# Sheet1.net
KiCad netlist of a schematic drawn in Altium Designer
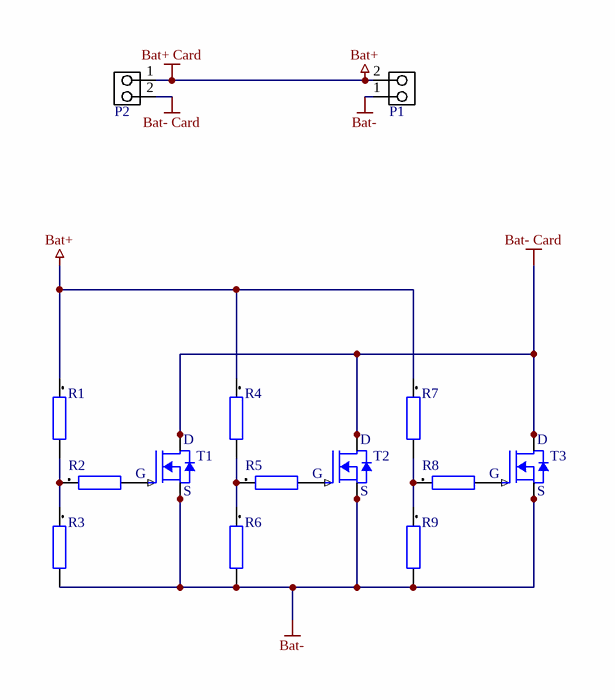
[diagram p0: Sheet1.SchDoc]

(export (version "E")
  (design (tool "Eeschema 10.0.6"))
  (components
    (comp (ref "P1")
      (value "2 power pads")
      (footprint "PowerPads 2 pins")
      (description "2-Pin")
      (fields (field (name "MANUFACTURER") "Generic Components") (field (name "PUBLISHER") "Altium Limited"))
      (libsource (lib "") (part "2 power pads_1"))
    )
    (comp (ref "P2")
      (value "2 power pads")
      (footprint "PowerPads 2 pins")
      (description "2-Pin")
      (fields (field (name "MANUFACTURER") "Generic Components") (field (name "PUBLISHER") "Altium Limited"))
      (libsource (lib "Schlib") (part "2 power pads"))
    )
    (comp (ref "R1")
      (value "TBD")
      (footprint "RESC1608X06L")
      (description "Resistor ToDo 0603")
      (libsource (lib "LSRO1Altium") (part "RES"))
    )
    (comp (ref "R2")
      (value "TBD")
      (footprint "RESC1608X06L")
      (description "Resistor ToDo 0603")
      (libsource (lib "LSRO1Altium") (part "RES"))
    )
    (comp (ref "R3")
      (value "TBD")
      (footprint "RESC1608X06L")
      (description "Resistor ToDo 0603")
      (libsource (lib "LSRO1Altium") (part "RES"))
    )
    (comp (ref "R4")
      (value "TBD")
      (footprint "RESC1608X06L")
      (description "Resistor ToDo 0603")
      (libsource (lib "LSRO1Altium") (part "RES"))
    )
    (comp (ref "R5")
      (value "TBD")
      (footprint "RESC1608X06L")
      (description "Resistor ToDo 0603")
      (libsource (lib "LSRO1Altium") (part "RES"))
    )
    (comp (ref "R6")
      (value "TBD")
      (footprint "RESC1608X06L")
      (description "Resistor ToDo 0603")
      (libsource (lib "LSRO1Altium") (part "RES"))
    )
    (comp (ref "R7")
      (value "TBD")
      (footprint "RESC1608X06L")
      (description "Resistor ToDo 0603")
      (libsource (lib "LSRO1Altium") (part "RES"))
    )
    (comp (ref "R8")
      (value "TBD")
      (footprint "RESC1608X06L")
      (description "Resistor ToDo 0603")
      (libsource (lib "LSRO1Altium") (part "RES"))
    )
    (comp (ref "R9")
      (value "TBD")
      (footprint "RESC1608X06L")
      (description "Resistor ToDo 0603")
      (libsource (lib "LSRO1Altium") (part "RES"))
    )
    (comp (ref "T1")
      (value "FDMC8010DC")
      (footprint "PQFN8 3.3X3.3")
      (fields (field (name "MANUFACTURER") "ON Semiconductor / Fairchild"))
      (libsource (lib "Schlib1") (part "FDMC8010DC"))
    )
    (comp (ref "T2")
      (value "FDMC8010DC")
      (footprint "PQFN8 3.3X3.3")
      (fields (field (name "MANUFACTURER") "ON Semiconductor / Fairchild"))
      (libsource (lib "Schlib1") (part "FDMC8010DC"))
    )
    (comp (ref "T3")
      (value "FDMC8010DC")
      (footprint "PQFN8 3.3X3.3")
      (fields (field (name "MANUFACTURER") "ON Semiconductor / Fairchild"))
      (libsource (lib "Schlib1") (part "FDMC8010DC"))
    )
  )
  (nets
    (net (code "1") (name "Bat+") (class "Default")
      (node (ref "P1") (pin "2") (pinfunction "2_2") (pintype "passive"))
      (node (ref "P2") (pin "1") (pinfunction "1_1") (pintype "passive"))
      (node (ref "R1") (pin "1") (pinfunction "1_1") (pintype "passive"))
      (node (ref "R4") (pin "1") (pinfunction "1_1") (pintype "passive"))
      (node (ref "R7") (pin "1") (pinfunction "1_1") (pintype "passive"))
    )
    (net (code "2") (name "Bat-") (class "Default")
      (node (ref "P1") (pin "1") (pinfunction "1_1") (pintype "passive"))
      (node (ref "R3") (pin "2") (pinfunction "2_2") (pintype "passive"))
      (node (ref "R6") (pin "2") (pinfunction "2_2") (pintype "passive"))
      (node (ref "R9") (pin "2") (pinfunction "2_2") (pintype "passive"))
      (node (ref "T1") (pin "1") (pinfunction "S_1") (pintype "passive"))
      (node (ref "T1") (pin "2") (pinfunction "S_2") (pintype "passive"))
      (node (ref "T1") (pin "3") (pinfunction "S_3") (pintype "passive"))
      (node (ref "T2") (pin "1") (pinfunction "S_1") (pintype "passive"))
      (node (ref "T2") (pin "2") (pinfunction "S_2") (pintype "passive"))
      (node (ref "T2") (pin "3") (pinfunction "S_3") (pintype "passive"))
      (node (ref "T3") (pin "1") (pinfunction "S_1") (pintype "passive"))
      (node (ref "T3") (pin "2") (pinfunction "S_2") (pintype "passive"))
      (node (ref "T3") (pin "3") (pinfunction "S_3") (pintype "passive"))
    )
    (net (code "3") (name "Bat- Card") (class "Default")
      (node (ref "P2") (pin "2") (pinfunction "2_2") (pintype "passive"))
      (node (ref "T1") (pin "5") (pinfunction "D_5") (pintype "passive"))
      (node (ref "T1") (pin "6") (pinfunction "D_6") (pintype "passive"))
      (node (ref "T1") (pin "7") (pinfunction "D_7") (pintype "passive"))
      (node (ref "T1") (pin "8") (pinfunction "D_8") (pintype "passive"))
      (node (ref "T1") (pin "9") (pinfunction "D_9") (pintype "passive"))
      (node (ref "T2") (pin "5") (pinfunction "D_5") (pintype "passive"))
      (node (ref "T2") (pin "6") (pinfunction "D_6") (pintype "passive"))
      (node (ref "T2") (pin "7") (pinfunction "D_7") (pintype "passive"))
      (node (ref "T2") (pin "8") (pinfunction "D_8") (pintype "passive"))
      (node (ref "T2") (pin "9") (pinfunction "D_9") (pintype "passive"))
      (node (ref "T3") (pin "5") (pinfunction "D_5") (pintype "passive"))
      (node (ref "T3") (pin "6") (pinfunction "D_6") (pintype "passive"))
      (node (ref "T3") (pin "7") (pinfunction "D_7") (pintype "passive"))
      (node (ref "T3") (pin "8") (pinfunction "D_8") (pintype "passive"))
      (node (ref "T3") (pin "9") (pinfunction "D_9") (pintype "passive"))
    )
    (net (code "4") (name "Net-(R1-Pad2)") (class "Default")
      (node (ref "R1") (pin "2") (pinfunction "2_2") (pintype "passive"))
      (node (ref "R2") (pin "1") (pinfunction "1_1") (pintype "passive"))
      (node (ref "R3") (pin "1") (pinfunction "1_1") (pintype "passive"))
    )
    (net (code "5") (name "Net-(R4-Pad2)") (class "Default")
      (node (ref "R4") (pin "2") (pinfunction "2_2") (pintype "passive"))
      (node (ref "R5") (pin "1") (pinfunction "1_1") (pintype "passive"))
      (node (ref "R6") (pin "1") (pinfunction "1_1") (pintype "passive"))
    )
    (net (code "6") (name "Net-(R7-Pad2)") (class "Default")
      (node (ref "R7") (pin "2") (pinfunction "2_2") (pintype "passive"))
      (node (ref "R8") (pin "1") (pinfunction "1_1") (pintype "passive"))
      (node (ref "R9") (pin "1") (pinfunction "1_1") (pintype "passive"))
    )
    (net (code "7") (name "Net-(T1-G)") (class "Default")
      (node (ref "R2") (pin "2") (pinfunction "2_2") (pintype "passive"))
      (node (ref "T1") (pin "4") (pinfunction "G_4") (pintype "input"))
    )
    (net (code "8") (name "Net-(T2-G)") (class "Default")
      (node (ref "R5") (pin "2") (pinfunction "2_2") (pintype "passive"))
      (node (ref "T2") (pin "4") (pinfunction "G_4") (pintype "input"))
    )
    (net (code "9") (name "Net-(T3-G)") (class "Default")
      (node (ref "R8") (pin "2") (pinfunction "2_2") (pintype "passive"))
      (node (ref "T3") (pin "4") (pinfunction "G_4") (pintype "input"))
    )
  )
)
